# eMMC.net
KiCad netlist of a schematic drawn in Altium Designer
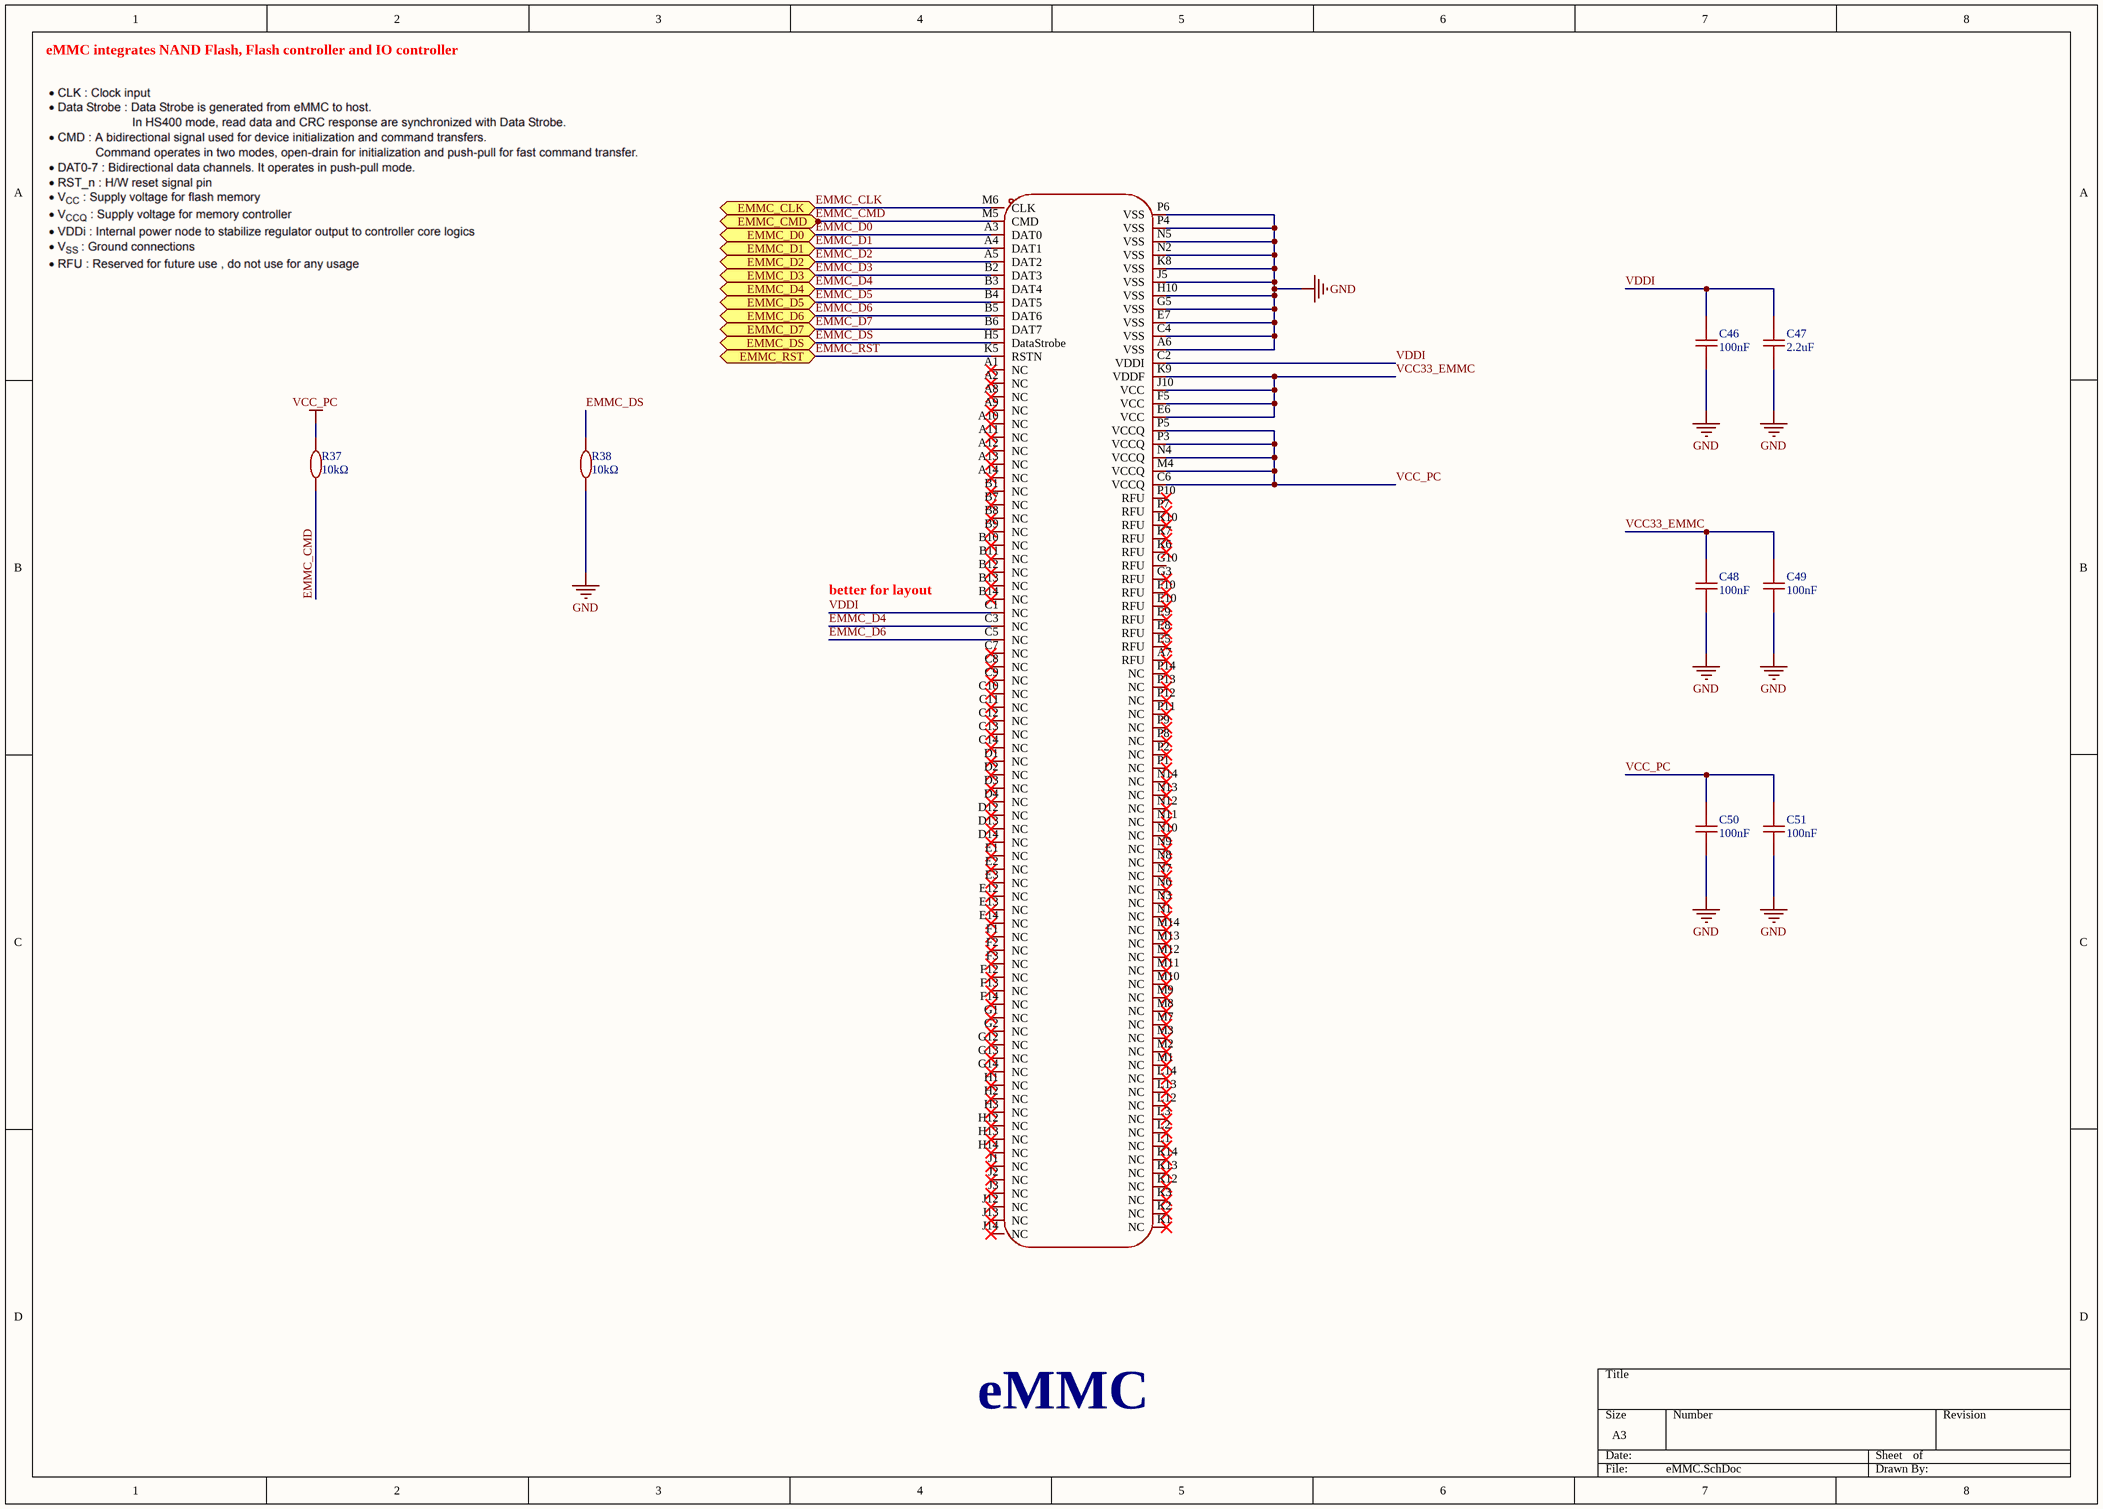
[diagram p0: eMMC.SchDoc]

(export (version "E")
  (design (tool "Eeschema 10.0.6"))
  (components
    (comp (ref "C46")
      (value "100nF")
      (footprint "C0402")
      (description "50V 100nF X7R ±10% 0402 Ceramic Capacitors ROHS")
      (libsource (lib "RLC") (part "100nF"))
    )
    (comp (ref "C47")
      (value "2.2uF")
      (footprint "C0402")
      (description "16V 2.2uF X5R ±10% 0402 Ceramic Capacitors ROHS")
      (libsource (lib "RLC") (part "2.2uF"))
    )
    (comp (ref "C48")
      (value "100nF")
      (footprint "C0402")
      (description "50V 100nF X7R ±10% 0402 Ceramic Capacitors ROHS")
      (libsource (lib "RLC") (part "100nF"))
    )
    (comp (ref "C49")
      (value "100nF")
      (footprint "C0402")
      (description "50V 100nF X7R ±10% 0402 Ceramic Capacitors ROHS")
      (libsource (lib "RLC") (part "100nF"))
    )
    (comp (ref "C50")
      (value "100nF")
      (footprint "C0402")
      (description "50V 100nF X7R ±10% 0402 Ceramic Capacitors ROHS")
      (libsource (lib "RLC") (part "100nF"))
    )
    (comp (ref "C51")
      (value "100nF")
      (footprint "C0402")
      (description "50V 100nF X7R ±10% 0402 Ceramic Capacitors ROHS")
      (libsource (lib "RLC") (part "100nF"))
    )
    (comp (ref "R37")
      (value "10kΩ")
      (footprint "R0402")
      (description "62.5mW 10kΩ 50V ±100ppm/℃ Thick Film Resistor ±1% 0402 Chip Resistor - Surface Mount ROHS")
      (libsource (lib "RLC") (part "10kΩ"))
    )
    (comp (ref "R38")
      (value "10kΩ")
      (footprint "R0402")
      (description "62.5mW 10kΩ 50V ±100ppm/℃ Thick Film Resistor ±1% 0402 Chip Resistor - Surface Mount ROHS")
      (libsource (lib "RLC") (part "10kΩ"))
    )
    (comp (ref "U3")
      (value "KLM8G1GETF-B041")
      (footprint "FBGA-153_L13.0-W11.5-P0.50_KLMAG1JETD-B041")
      (description "8GB 2.7V~3.6V eMMC 5.1 330/50 MB/s FBGA-153(11.5x13) Memory (ICs) ROHS")
      (fields (field (name "MANUFACTURER") "SAMSUNG(三星半导体)"))
      (libsource (lib "IC") (part "KLM8G1GETF-B041_1"))
    )
  )
  (nets
    (net (code "1") (name "/EMMC_CLK") (class "Default")
      (node (ref "U3") (pin "M6") (pinfunction "CLK_M6") (pintype "passive"))
    )
    (net (code "2") (name "/EMMC_CMD") (class "Default")
      (node (ref "R37") (pin "1") (pinfunction "1_1") (pintype "passive"))
      (node (ref "U3") (pin "M5") (pinfunction "CMD_M5") (pintype "passive"))
    )
    (net (code "3") (name "/EMMC_D0") (class "Default")
      (node (ref "U3") (pin "A3") (pinfunction "DAT0_A3") (pintype "passive"))
    )
    (net (code "4") (name "/EMMC_D1") (class "Default")
      (node (ref "U3") (pin "A4") (pinfunction "DAT1_A4") (pintype "passive"))
    )
    (net (code "5") (name "/EMMC_D2") (class "Default")
      (node (ref "U3") (pin "A5") (pinfunction "DAT2_A5") (pintype "passive"))
    )
    (net (code "6") (name "/EMMC_D3") (class "Default")
      (node (ref "U3") (pin "B2") (pinfunction "DAT3_B2") (pintype "passive"))
    )
    (net (code "7") (name "/EMMC_D4") (class "Default")
      (node (ref "U3") (pin "B3") (pinfunction "DAT4_B3") (pintype "passive"))
      (node (ref "U3") (pin "C3") (pinfunction "NC_C3") (pintype "passive"))
    )
    (net (code "8") (name "/EMMC_D5") (class "Default")
      (node (ref "U3") (pin "B4") (pinfunction "DAT5_B4") (pintype "passive"))
    )
    (net (code "9") (name "/EMMC_D6") (class "Default")
      (node (ref "U3") (pin "B5") (pinfunction "DAT6_B5") (pintype "passive"))
      (node (ref "U3") (pin "C5") (pinfunction "NC_C5") (pintype "passive"))
    )
    (net (code "10") (name "/EMMC_D7") (class "Default")
      (node (ref "U3") (pin "B6") (pinfunction "DAT7_B6") (pintype "passive"))
    )
    (net (code "11") (name "/EMMC_DS") (class "Default")
      (node (ref "R38") (pin "2") (pinfunction "2_2") (pintype "passive"))
      (node (ref "U3") (pin "H5") (pinfunction "DataStrobe_H5") (pintype "passive"))
    )
    (net (code "12") (name "/EMMC_RST") (class "Default")
      (node (ref "U3") (pin "K5") (pinfunction "RSTN_K5") (pintype "passive"))
    )
    (net (code "13") (name "/VCC33_EMMC") (class "Default")
      (node (ref "C48") (pin "2") (pinfunction "2_2") (pintype "passive"))
      (node (ref "C49") (pin "2") (pinfunction "2_2") (pintype "passive"))
      (node (ref "U3") (pin "E6") (pinfunction "VCC_E6") (pintype "passive"))
      (node (ref "U3") (pin "F5") (pinfunction "VCC_F5") (pintype "passive"))
      (node (ref "U3") (pin "J10") (pinfunction "VCC_J10") (pintype "passive"))
      (node (ref "U3") (pin "K9") (pinfunction "VDDF_K9") (pintype "passive"))
    )
    (net (code "14") (name "/VDDI") (class "Default")
      (node (ref "C46") (pin "2") (pinfunction "2_2") (pintype "passive"))
      (node (ref "C47") (pin "2") (pinfunction "2_2") (pintype "passive"))
      (node (ref "U3") (pin "C1") (pinfunction "NC_C1") (pintype "passive"))
      (node (ref "U3") (pin "C2") (pinfunction "VDDI_C2") (pintype "passive"))
    )
    (net (code "15") (name "GND") (class "Default")
      (node (ref "C46") (pin "1") (pinfunction "1_1") (pintype "passive"))
      (node (ref "C47") (pin "1") (pinfunction "1_1") (pintype "passive"))
      (node (ref "C48") (pin "1") (pinfunction "1_1") (pintype "passive"))
      (node (ref "C49") (pin "1") (pinfunction "1_1") (pintype "passive"))
      (node (ref "C50") (pin "1") (pinfunction "1_1") (pintype "passive"))
      (node (ref "C51") (pin "1") (pinfunction "1_1") (pintype "passive"))
      (node (ref "R38") (pin "1") (pinfunction "1_1") (pintype "passive"))
      (node (ref "U3") (pin "A6") (pinfunction "VSS_A6") (pintype "passive"))
      (node (ref "U3") (pin "C4") (pinfunction "VSS_C4") (pintype "passive"))
      (node (ref "U3") (pin "E7") (pinfunction "VSS_E7") (pintype "passive"))
      (node (ref "U3") (pin "G5") (pinfunction "VSS_G5") (pintype "passive"))
      (node (ref "U3") (pin "H10") (pinfunction "VSS_H10") (pintype "passive"))
      (node (ref "U3") (pin "J5") (pinfunction "VSS_J5") (pintype "passive"))
      (node (ref "U3") (pin "K8") (pinfunction "VSS_K8") (pintype "passive"))
      (node (ref "U3") (pin "N2") (pinfunction "VSS_N2") (pintype "passive"))
      (node (ref "U3") (pin "N5") (pinfunction "VSS_N5") (pintype "passive"))
      (node (ref "U3") (pin "P4") (pinfunction "VSS_P4") (pintype "passive"))
      (node (ref "U3") (pin "P6") (pinfunction "VSS_P6") (pintype "passive"))
    )
    (net (code "16") (name "VCC_PC") (class "Default")
      (node (ref "C50") (pin "2") (pinfunction "2_2") (pintype "passive"))
      (node (ref "C51") (pin "2") (pinfunction "2_2") (pintype "passive"))
      (node (ref "R37") (pin "2") (pinfunction "2_2") (pintype "passive"))
      (node (ref "U3") (pin "C6") (pinfunction "VCCQ_C6") (pintype "passive"))
      (node (ref "U3") (pin "M4") (pinfunction "VCCQ_M4") (pintype "passive"))
      (node (ref "U3") (pin "N4") (pinfunction "VCCQ_N4") (pintype "passive"))
      (node (ref "U3") (pin "P3") (pinfunction "VCCQ_P3") (pintype "passive"))
      (node (ref "U3") (pin "P5") (pinfunction "VCCQ_P5") (pintype "passive"))
    )
    (net (code "17") (name "unconnected-(U3-NC-PadA1)") (class "Default")
      (node (ref "U3") (pin "A1") (pinfunction "NC_A1") (pintype "passive+no_connect"))
    )
    (net (code "18") (name "unconnected-(U3-NC-PadA2)") (class "Default")
      (node (ref "U3") (pin "A2") (pinfunction "NC_A2") (pintype "passive+no_connect"))
    )
    (net (code "19") (name "unconnected-(U3-NC-PadA8)") (class "Default")
      (node (ref "U3") (pin "A8") (pinfunction "NC_A8") (pintype "passive+no_connect"))
    )
    (net (code "20") (name "unconnected-(U3-NC-PadA9)") (class "Default")
      (node (ref "U3") (pin "A9") (pinfunction "NC_A9") (pintype "passive+no_connect"))
    )
    (net (code "21") (name "unconnected-(U3-NC-PadA10)") (class "Default")
      (node (ref "U3") (pin "A10") (pinfunction "NC_A10") (pintype "passive+no_connect"))
    )
    (net (code "22") (name "unconnected-(U3-NC-PadA11)") (class "Default")
      (node (ref "U3") (pin "A11") (pinfunction "NC_A11") (pintype "passive+no_connect"))
    )
    (net (code "23") (name "unconnected-(U3-NC-PadA12)") (class "Default")
      (node (ref "U3") (pin "A12") (pinfunction "NC_A12") (pintype "passive+no_connect"))
    )
    (net (code "24") (name "unconnected-(U3-NC-PadA13)") (class "Default")
      (node (ref "U3") (pin "A13") (pinfunction "NC_A13") (pintype "passive+no_connect"))
    )
    (net (code "25") (name "unconnected-(U3-NC-PadA14)") (class "Default")
      (node (ref "U3") (pin "A14") (pinfunction "NC_A14") (pintype "passive+no_connect"))
    )
    (net (code "26") (name "unconnected-(U3-NC-PadB1)") (class "Default")
      (node (ref "U3") (pin "B1") (pinfunction "NC_B1") (pintype "passive+no_connect"))
    )
    (net (code "27") (name "unconnected-(U3-NC-PadB7)") (class "Default")
      (node (ref "U3") (pin "B7") (pinfunction "NC_B7") (pintype "passive+no_connect"))
    )
    (net (code "28") (name "unconnected-(U3-NC-PadB8)") (class "Default")
      (node (ref "U3") (pin "B8") (pinfunction "NC_B8") (pintype "passive+no_connect"))
    )
    (net (code "29") (name "unconnected-(U3-NC-PadB9)") (class "Default")
      (node (ref "U3") (pin "B9") (pinfunction "NC_B9") (pintype "passive+no_connect"))
    )
    (net (code "30") (name "unconnected-(U3-NC-PadB10)") (class "Default")
      (node (ref "U3") (pin "B10") (pinfunction "NC_B10") (pintype "passive+no_connect"))
    )
    (net (code "31") (name "unconnected-(U3-NC-PadB11)") (class "Default")
      (node (ref "U3") (pin "B11") (pinfunction "NC_B11") (pintype "passive+no_connect"))
    )
    (net (code "32") (name "unconnected-(U3-NC-PadB12)") (class "Default")
      (node (ref "U3") (pin "B12") (pinfunction "NC_B12") (pintype "passive+no_connect"))
    )
    (net (code "33") (name "unconnected-(U3-NC-PadB13)") (class "Default")
      (node (ref "U3") (pin "B13") (pinfunction "NC_B13") (pintype "passive+no_connect"))
    )
    (net (code "34") (name "unconnected-(U3-NC-PadB14)") (class "Default")
      (node (ref "U3") (pin "B14") (pinfunction "NC_B14") (pintype "passive+no_connect"))
    )
    (net (code "35") (name "unconnected-(U3-NC-PadC7)") (class "Default")
      (node (ref "U3") (pin "C7") (pinfunction "NC_C7") (pintype "passive+no_connect"))
    )
    (net (code "36") (name "unconnected-(U3-NC-PadC8)") (class "Default")
      (node (ref "U3") (pin "C8") (pinfunction "NC_C8") (pintype "passive+no_connect"))
    )
    (net (code "37") (name "unconnected-(U3-NC-PadC9)") (class "Default")
      (node (ref "U3") (pin "C9") (pinfunction "NC_C9") (pintype "passive+no_connect"))
    )
    (net (code "38") (name "unconnected-(U3-NC-PadC10)") (class "Default")
      (node (ref "U3") (pin "C10") (pinfunction "NC_C10") (pintype "passive+no_connect"))
    )
    (net (code "39") (name "unconnected-(U3-NC-PadC11)") (class "Default")
      (node (ref "U3") (pin "C11") (pinfunction "NC_C11") (pintype "passive+no_connect"))
    )
    (net (code "40") (name "unconnected-(U3-NC-PadC12)") (class "Default")
      (node (ref "U3") (pin "C12") (pinfunction "NC_C12") (pintype "passive+no_connect"))
    )
    (net (code "41") (name "unconnected-(U3-NC-PadC13)") (class "Default")
      (node (ref "U3") (pin "C13") (pinfunction "NC_C13") (pintype "passive+no_connect"))
    )
    (net (code "42") (name "unconnected-(U3-NC-PadC14)") (class "Default")
      (node (ref "U3") (pin "C14") (pinfunction "NC_C14") (pintype "passive+no_connect"))
    )
    (net (code "43") (name "unconnected-(U3-NC-PadD1)") (class "Default")
      (node (ref "U3") (pin "D1") (pinfunction "NC_D1") (pintype "passive+no_connect"))
    )
    (net (code "44") (name "unconnected-(U3-NC-PadD2)") (class "Default")
      (node (ref "U3") (pin "D2") (pinfunction "NC_D2") (pintype "passive+no_connect"))
    )
    (net (code "45") (name "unconnected-(U3-NC-PadD3)") (class "Default")
      (node (ref "U3") (pin "D3") (pinfunction "NC_D3") (pintype "passive+no_connect"))
    )
    (net (code "46") (name "unconnected-(U3-NC-PadD4)") (class "Default")
      (node (ref "U3") (pin "D4") (pinfunction "NC_D4") (pintype "passive+no_connect"))
    )
    (net (code "47") (name "unconnected-(U3-NC-PadD12)") (class "Default")
      (node (ref "U3") (pin "D12") (pinfunction "NC_D12") (pintype "passive+no_connect"))
    )
    (net (code "48") (name "unconnected-(U3-NC-PadD13)") (class "Default")
      (node (ref "U3") (pin "D13") (pinfunction "NC_D13") (pintype "passive+no_connect"))
    )
    (net (code "49") (name "unconnected-(U3-NC-PadD14)") (class "Default")
      (node (ref "U3") (pin "D14") (pinfunction "NC_D14") (pintype "passive+no_connect"))
    )
    (net (code "50") (name "unconnected-(U3-NC-PadE1)") (class "Default")
      (node (ref "U3") (pin "E1") (pinfunction "NC_E1") (pintype "passive+no_connect"))
    )
    (net (code "51") (name "unconnected-(U3-NC-PadE2)") (class "Default")
      (node (ref "U3") (pin "E2") (pinfunction "NC_E2") (pintype "passive+no_connect"))
    )
    (net (code "52") (name "unconnected-(U3-NC-PadE3)") (class "Default")
      (node (ref "U3") (pin "E3") (pinfunction "NC_E3") (pintype "passive+no_connect"))
    )
    (net (code "53") (name "unconnected-(U3-NC-PadE12)") (class "Default")
      (node (ref "U3") (pin "E12") (pinfunction "NC_E12") (pintype "passive+no_connect"))
    )
    (net (code "54") (name "unconnected-(U3-NC-PadE13)") (class "Default")
      (node (ref "U3") (pin "E13") (pinfunction "NC_E13") (pintype "passive+no_connect"))
    )
    (net (code "55") (name "unconnected-(U3-NC-PadE14)") (class "Default")
      (node (ref "U3") (pin "E14") (pinfunction "NC_E14") (pintype "passive+no_connect"))
    )
    (net (code "56") (name "unconnected-(U3-NC-PadF1)") (class "Default")
      (node (ref "U3") (pin "F1") (pinfunction "NC_F1") (pintype "passive+no_connect"))
    )
    (net (code "57") (name "unconnected-(U3-NC-PadF2)") (class "Default")
      (node (ref "U3") (pin "F2") (pinfunction "NC_F2") (pintype "passive+no_connect"))
    )
    (net (code "58") (name "unconnected-(U3-NC-PadF3)") (class "Default")
      (node (ref "U3") (pin "F3") (pinfunction "NC_F3") (pintype "passive+no_connect"))
    )
    (net (code "59") (name "unconnected-(U3-NC-PadF12)") (class "Default")
      (node (ref "U3") (pin "F12") (pinfunction "NC_F12") (pintype "passive+no_connect"))
    )
    (net (code "60") (name "unconnected-(U3-NC-PadF13)") (class "Default")
      (node (ref "U3") (pin "F13") (pinfunction "NC_F13") (pintype "passive+no_connect"))
    )
    (net (code "61") (name "unconnected-(U3-NC-PadF14)") (class "Default")
      (node (ref "U3") (pin "F14") (pinfunction "NC_F14") (pintype "passive+no_connect"))
    )
    (net (code "62") (name "unconnected-(U3-NC-PadG1)") (class "Default")
      (node (ref "U3") (pin "G1") (pinfunction "NC_G1") (pintype "passive+no_connect"))
    )
    (net (code "63") (name "unconnected-(U3-NC-PadG2)") (class "Default")
      (node (ref "U3") (pin "G2") (pinfunction "NC_G2") (pintype "passive+no_connect"))
    )
    (net (code "64") (name "unconnected-(U3-NC-PadG12)") (class "Default")
      (node (ref "U3") (pin "G12") (pinfunction "NC_G12") (pintype "passive+no_connect"))
    )
    (net (code "65") (name "unconnected-(U3-NC-PadG13)") (class "Default")
      (node (ref "U3") (pin "G13") (pinfunction "NC_G13") (pintype "passive+no_connect"))
    )
    (net (code "66") (name "unconnected-(U3-NC-PadG14)") (class "Default")
      (node (ref "U3") (pin "G14") (pinfunction "NC_G14") (pintype "passive+no_connect"))
    )
    (net (code "67") (name "unconnected-(U3-NC-PadH1)") (class "Default")
      (node (ref "U3") (pin "H1") (pinfunction "NC_H1") (pintype "passive+no_connect"))
    )
    (net (code "68") (name "unconnected-(U3-NC-PadH2)") (class "Default")
      (node (ref "U3") (pin "H2") (pinfunction "NC_H2") (pintype "passive+no_connect"))
    )
    (net (code "69") (name "unconnected-(U3-NC-PadH3)") (class "Default")
      (node (ref "U3") (pin "H3") (pinfunction "NC_H3") (pintype "passive+no_connect"))
    )
    (net (code "70") (name "unconnected-(U3-NC-PadH12)") (class "Default")
      (node (ref "U3") (pin "H12") (pinfunction "NC_H12") (pintype "passive+no_connect"))
    )
    (net (code "71") (name "unconnected-(U3-NC-PadH13)") (class "Default")
      (node (ref "U3") (pin "H13") (pinfunction "NC_H13") (pintype "passive+no_connect"))
    )
    (net (code "72") (name "unconnected-(U3-NC-PadH14)") (class "Default")
      (node (ref "U3") (pin "H14") (pinfunction "NC_H14") (pintype "passive+no_connect"))
    )
    (net (code "73") (name "unconnected-(U3-NC-PadJ1)") (class "Default")
      (node (ref "U3") (pin "J1") (pinfunction "NC_J1") (pintype "passive+no_connect"))
    )
    (net (code "74") (name "unconnected-(U3-NC-PadJ2)") (class "Default")
      (node (ref "U3") (pin "J2") (pinfunction "NC_J2") (pintype "passive+no_connect"))
    )
    (net (code "75") (name "unconnected-(U3-NC-PadJ3)") (class "Default")
      (node (ref "U3") (pin "J3") (pinfunction "NC_J3") (pintype "passive+no_connect"))
    )
    (net (code "76") (name "unconnected-(U3-NC-PadJ12)") (class "Default")
      (node (ref "U3") (pin "J12") (pinfunction "NC_J12") (pintype "passive+no_connect"))
    )
    (net (code "77") (name "unconnected-(U3-NC-PadJ13)") (class "Default")
      (node (ref "U3") (pin "J13") (pinfunction "NC_J13") (pintype "passive+no_connect"))
    )
    (net (code "78") (name "unconnected-(U3-NC-PadJ14)") (class "Default")
      (node (ref "U3") (pin "J14") (pinfunction "NC_J14") (pintype "passive+no_connect"))
    )
    (net (code "79") (name "unconnected-(U3-NC-PadK1)") (class "Default")
      (node (ref "U3") (pin "K1") (pinfunction "NC_K1") (pintype "passive+no_connect"))
    )
    (net (code "80") (name "unconnected-(U3-NC-PadK2)") (class "Default")
      (node (ref "U3") (pin "K2") (pinfunction "NC_K2") (pintype "passive+no_connect"))
    )
    (net (code "81") (name "unconnected-(U3-NC-PadK3)") (class "Default")
      (node (ref "U3") (pin "K3") (pinfunction "NC_K3") (pintype "passive+no_connect"))
    )
    (net (code "82") (name "unconnected-(U3-NC-PadK12)") (class "Default")
      (node (ref "U3") (pin "K12") (pinfunction "NC_K12") (pintype "passive+no_connect"))
    )
    (net (code "83") (name "unconnected-(U3-NC-PadK13)") (class "Default")
      (node (ref "U3") (pin "K13") (pinfunction "NC_K13") (pintype "passive+no_connect"))
    )
    (net (code "84") (name "unconnected-(U3-NC-PadK14)") (class "Default")
      (node (ref "U3") (pin "K14") (pinfunction "NC_K14") (pintype "passive+no_connect"))
    )
    (net (code "85") (name "unconnected-(U3-NC-PadL1)") (class "Default")
      (node (ref "U3") (pin "L1") (pinfunction "NC_L1") (pintype "passive+no_connect"))
    )
    (net (code "86") (name "unconnected-(U3-NC-PadL2)") (class "Default")
      (node (ref "U3") (pin "L2") (pinfunction "NC_L2") (pintype "passive+no_connect"))
    )
    (net (code "87") (name "unconnected-(U3-NC-PadL3)") (class "Default")
      (node (ref "U3") (pin "L3") (pinfunction "NC_L3") (pintype "passive+no_connect"))
    )
    (net (code "88") (name "unconnected-(U3-NC-PadL12)") (class "Default")
      (node (ref "U3") (pin "L12") (pinfunction "NC_L12") (pintype "passive+no_connect"))
    )
    (net (code "89") (name "unconnected-(U3-NC-PadL13)") (class "Default")
      (node (ref "U3") (pin "L13") (pinfunction "NC_L13") (pintype "passive+no_connect"))
    )
    (net (code "90") (name "unconnected-(U3-NC-PadL14)") (class "Default")
      (node (ref "U3") (pin "L14") (pinfunction "NC_L14") (pintype "passive+no_connect"))
    )
    (net (code "91") (name "unconnected-(U3-NC-PadM1)") (class "Default")
      (node (ref "U3") (pin "M1") (pinfunction "NC_M1") (pintype "passive+no_connect"))
    )
    (net (code "92") (name "unconnected-(U3-NC-PadM2)") (class "Default")
      (node (ref "U3") (pin "M2") (pinfunction "NC_M2") (pintype "passive+no_connect"))
    )
    (net (code "93") (name "unconnected-(U3-NC-PadM3)") (class "Default")
      (node (ref "U3") (pin "M3") (pinfunction "NC_M3") (pintype "passive+no_connect"))
    )
    (net (code "94") (name "unconnected-(U3-NC-PadM7)") (class "Default")
      (node (ref "U3") (pin "M7") (pinfunction "NC_M7") (pintype "passive+no_connect"))
    )
    (net (code "95") (name "unconnected-(U3-NC-PadM8)") (class "Default")
      (node (ref "U3") (pin "M8") (pinfunction "NC_M8") (pintype "passive+no_connect"))
    )
    (net (code "96") (name "unconnected-(U3-NC-PadM9)") (class "Default")
      (node (ref "U3") (pin "M9") (pinfunction "NC_M9") (pintype "passive+no_connect"))
    )
    (net (code "97") (name "unconnected-(U3-NC-PadM10)") (class "Default")
      (node (ref "U3") (pin "M10") (pinfunction "NC_M10") (pintype "passive+no_connect"))
    )
    (net (code "98") (name "unconnected-(U3-NC-PadM11)") (class "Default")
      (node (ref "U3") (pin "M11") (pinfunction "NC_M11") (pintype "passive+no_connect"))
    )
    (net (code "99") (name "unconnected-(U3-NC-PadM12)") (class "Default")
      (node (ref "U3") (pin "M12") (pinfunction "NC_M12") (pintype "passive+no_connect"))
    )
    (net (code "100") (name "unconnected-(U3-NC-PadM13)") (class "Default")
      (node (ref "U3") (pin "M13") (pinfunction "NC_M13") (pintype "passive+no_connect"))
    )
    (net (code "101") (name "unconnected-(U3-NC-PadM14)") (class "Default")
      (node (ref "U3") (pin "M14") (pinfunction "NC_M14") (pintype "passive+no_connect"))
    )
    (net (code "102") (name "unconnected-(U3-NC-PadN1)") (class "Default")
      (node (ref "U3") (pin "N1") (pinfunction "NC_N1") (pintype "passive+no_connect"))
    )
    (net (code "103") (name "unconnected-(U3-NC-PadN3)") (class "Default")
      (node (ref "U3") (pin "N3") (pinfunction "NC_N3") (pintype "passive+no_connect"))
    )
    (net (code "104") (name "unconnected-(U3-NC-PadN6)") (class "Default")
      (node (ref "U3") (pin "N6") (pinfunction "NC_N6") (pintype "passive+no_connect"))
    )
    (net (code "105") (name "unconnected-(U3-NC-PadN7)") (class "Default")
      (node (ref "U3") (pin "N7") (pinfunction "NC_N7") (pintype "passive+no_connect"))
    )
    (net (code "106") (name "unconnected-(U3-NC-PadN8)") (class "Default")
      (node (ref "U3") (pin "N8") (pinfunction "NC_N8") (pintype "passive+no_connect"))
    )
    (net (code "107") (name "unconnected-(U3-NC-PadN9)") (class "Default")
      (node (ref "U3") (pin "N9") (pinfunction "NC_N9") (pintype "passive+no_connect"))
    )
    (net (code "108") (name "unconnected-(U3-NC-PadN10)") (class "Default")
      (node (ref "U3") (pin "N10") (pinfunction "NC_N10") (pintype "passive+no_connect"))
    )
    (net (code "109") (name "unconnected-(U3-NC-PadN11)") (class "Default")
      (node (ref "U3") (pin "N11") (pinfunction "NC_N11") (pintype "passive+no_connect"))
    )
    (net (code "110") (name "unconnected-(U3-NC-PadN12)") (class "Default")
      (node (ref "U3") (pin "N12") (pinfunction "NC_N12") (pintype "passive+no_connect"))
    )
    (net (code "111") (name "unconnected-(U3-NC-PadN13)") (class "Default")
      (node (ref "U3") (pin "N13") (pinfunction "NC_N13") (pintype "passive+no_connect"))
    )
    (net (code "112") (name "unconnected-(U3-NC-PadN14)") (class "Default")
      (node (ref "U3") (pin "N14") (pinfunction "NC_N14") (pintype "passive+no_connect"))
    )
    (net (code "113") (name "unconnected-(U3-NC-PadP1)") (class "Default")
      (node (ref "U3") (pin "P1") (pinfunction "NC_P1") (pintype "passive+no_connect"))
    )
    (net (code "114") (name "unconnected-(U3-NC-PadP2)") (class "Default")
      (node (ref "U3") (pin "P2") (pinfunction "NC_P2") (pintype "passive+no_connect"))
    )
    (net (code "115") (name "unconnected-(U3-NC-PadP8)") (class "Default")
      (node (ref "U3") (pin "P8") (pinfunction "NC_P8") (pintype "passive+no_connect"))
    )
    (net (code "116") (name "unconnected-(U3-NC-PadP9)") (class "Default")
      (node (ref "U3") (pin "P9") (pinfunction "NC_P9") (pintype "passive+no_connect"))
    )
    (net (code "117") (name "unconnected-(U3-NC-PadP11)") (class "Default")
      (node (ref "U3") (pin "P11") (pinfunction "NC_P11") (pintype "passive+no_connect"))
    )
    (net (code "118") (name "unconnected-(U3-NC-PadP12)") (class "Default")
      (node (ref "U3") (pin "P12") (pinfunction "NC_P12") (pintype "passive+no_connect"))
    )
    (net (code "119") (name "unconnected-(U3-NC-PadP13)") (class "Default")
      (node (ref "U3") (pin "P13") (pinfunction "NC_P13") (pintype "passive+no_connect"))
    )
    (net (code "120") (name "unconnected-(U3-NC-PadP14)") (class "Default")
      (node (ref "U3") (pin "P14") (pinfunction "NC_P14") (pintype "passive+no_connect"))
    )
    (net (code "121") (name "unconnected-(U3-RFU-PadA7)") (class "Default")
      (node (ref "U3") (pin "A7") (pinfunction "RFU_A7") (pintype "passive+no_connect"))
    )
    (net (code "122") (name "unconnected-(U3-RFU-PadE5)") (class "Default")
      (node (ref "U3") (pin "E5") (pinfunction "RFU_E5") (pintype "passive+no_connect"))
    )
    (net (code "123") (name "unconnected-(U3-RFU-PadE8)") (class "Default")
      (node (ref "U3") (pin "E8") (pinfunction "RFU_E8") (pintype "passive+no_connect"))
    )
    (net (code "124") (name "unconnected-(U3-RFU-PadE9)") (class "Default")
      (node (ref "U3") (pin "E9") (pinfunction "RFU_E9") (pintype "passive+no_connect"))
    )
    (net (code "125") (name "unconnected-(U3-RFU-PadE10)") (class "Default")
      (node (ref "U3") (pin "E10") (pinfunction "RFU_E10") (pintype "passive+no_connect"))
    )
    (net (code "126") (name "unconnected-(U3-RFU-PadF10)") (class "Default")
      (node (ref "U3") (pin "F10") (pinfunction "RFU_F10") (pintype "passive+no_connect"))
    )
    (net (code "127") (name "unconnected-(U3-RFU-PadG3)") (class "Default")
      (node (ref "U3") (pin "G3") (pinfunction "RFU_G3") (pintype "passive+no_connect"))
    )
    (net (code "128") (name "unconnected-(U3-RFU-PadG10)") (class "Default")
      (node (ref "U3") (pin "G10") (pinfunction "RFU_G10") (pintype "passive"))
    )
    (net (code "129") (name "unconnected-(U3-RFU-PadK6)") (class "Default")
      (node (ref "U3") (pin "K6") (pinfunction "RFU_K6") (pintype "passive+no_connect"))
    )
    (net (code "130") (name "unconnected-(U3-RFU-PadK7)") (class "Default")
      (node (ref "U3") (pin "K7") (pinfunction "RFU_K7") (pintype "passive+no_connect"))
    )
    (net (code "131") (name "unconnected-(U3-RFU-PadK10)") (class "Default")
      (node (ref "U3") (pin "K10") (pinfunction "RFU_K10") (pintype "passive+no_connect"))
    )
    (net (code "132") (name "unconnected-(U3-RFU-PadP7)") (class "Default")
      (node (ref "U3") (pin "P7") (pinfunction "RFU_P7") (pintype "passive+no_connect"))
    )
    (net (code "133") (name "unconnected-(U3-RFU-PadP10)") (class "Default")
      (node (ref "U3") (pin "P10") (pinfunction "RFU_P10") (pintype "passive+no_connect"))
    )
  )
)
